# DaughterBoard.net
KiCad netlist of a schematic drawn in Altium Designer
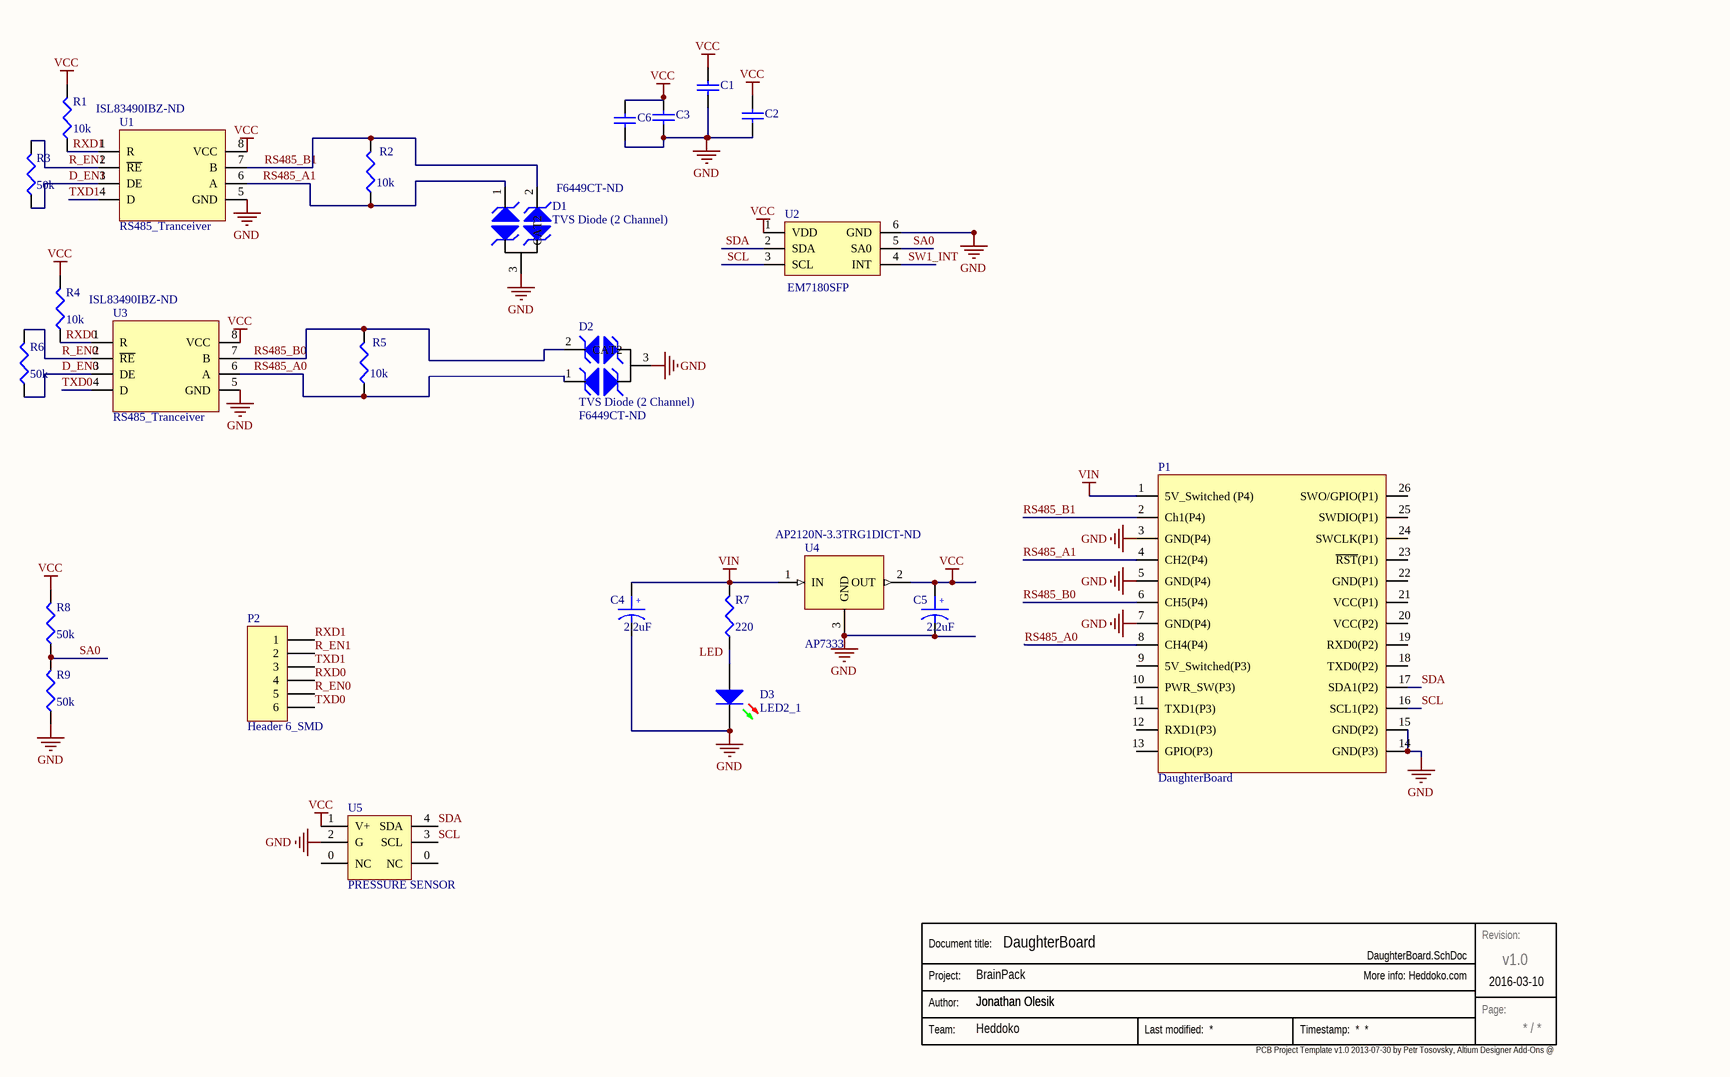
[diagram p0: DaughterBoard.SchDoc]

(export (version "E")
  (design (tool "Eeschema 10.0.6"))
  (components
    (comp (ref "C1")
      (value "Cap")
      (footprint "0603")
      (description "Capacitor")
      (fields (field (name "PUBLISHER") "Altium Limited"))
      (libsource (lib "SenaCorpLibSCH") (part "Cap"))
    )
    (comp (ref "C2")
      (value "Cap")
      (footprint "0603")
      (description "Capacitor")
      (fields (field (name "PUBLISHER") "Altium Limited"))
      (libsource (lib "SenaCorpLibSCH") (part "Cap"))
    )
    (comp (ref "C3")
      (value "Cap")
      (footprint "0603")
      (description "Capacitor")
      (fields (field (name "PUBLISHER") "Altium Limited"))
      (libsource (lib "SenaCorpLibSCH") (part "Cap"))
    )
    (comp (ref "C4")
      (value "2.2uF")
      (footprint "SMD0805")
      (fields
        (field (name "TOLERANCE") "±20%")
        (field (name "MANUFACTURER") "AVX Corporation")
        (field (name "MANUFACTURER PART NUMBER") "F921A225MPA")
      )
      (libsource (lib "AltiumDbLib") (part "CAP-POL"))
    )
    (comp (ref "C5")
      (value "2.2uF")
      (footprint "SMD0805")
      (fields
        (field (name "TOLERANCE") "±20%")
        (field (name "MANUFACTURER") "AVX Corporation")
        (field (name "MANUFACTURER PART NUMBER") "F921A225MPA")
      )
      (libsource (lib "AltiumDbLib") (part "CAP-POL"))
    )
    (comp (ref "C6")
      (value "Cap")
      (footprint "0603")
      (description "Capacitor")
      (fields (field (name "PUBLISHER") "Altium Limited"))
      (libsource (lib "SenaCorpLibSCH") (part "Cap"))
    )
    (comp (ref "D1")
      (value "TVS Diode (2 Channel)")
      (footprint "SOT23-3")
      (fields
        (field (name "SUPPLIER PART NUMBER") "F6449CT-ND")
        (field (name "MANUFACTURER PART NUMBER") "SM24CANA-02HTG")
        (field (name "MANUFACTURER") "Littelfuse Inc.")
      )
      (libsource (lib "SenaCorpLibSCH") (part "TVS Diode (2 Channel)"))
    )
    (comp (ref "D2")
      (value "TVS Diode (2 Channel)")
      (footprint "SOT23-3")
      (fields
        (field (name "SUPPLIER PART NUMBER") "F6449CT-ND")
        (field (name "MANUFACTURER PART NUMBER") "SM24CANA-02HTG")
        (field (name "MANUFACTURER") "Littelfuse Inc.")
      )
      (libsource (lib "SenaCorpLibSCH") (part "TVS Diode (2 Channel)"))
    )
    (comp (ref "D3")
      (value "LED2_1")
      (footprint "LED0603")
      (description "Typical RED, GREEN, YELLOW, AMBER GaAs LED")
      (fields (field (name "PUBLISHER") "Altium Limited"))
      (libsource (lib "SenaCorpLibSCH") (part "LED2_1"))
    )
    (comp (ref "P1")
      (value "DaughterBoard")
      (footprint "PowerBoardDaughter")
      (libsource (lib "SenaCorpLibSCH") (part "DaughterBoard"))
    )
    (comp (ref "P2")
      (value "Header 6_SMD")
      (footprint "Header 6 1.27mm")
      (description "Header, 6-Pin SMD")
      (fields (field (name "PUBLISHER") "Altium Limited"))
      (libsource (lib "SenaCorpLibSCH") (part "Header 6_SMD"))
    )
    (comp (ref "R1")
      (value "10k")
      (footprint "0603")
      (description "Resistor")
      (fields (field (name "PUBLISHER") "Altium Limited"))
      (libsource (lib "SenaCorpLibSCH") (part "Res3"))
    )
    (comp (ref "R2")
      (value "10k")
      (footprint "0402")
      (description "Resistor")
      (fields (field (name "PUBLISHER") "Altium Limited"))
      (libsource (lib "SenaCorpLibSCH") (part "Res3"))
    )
    (comp (ref "R3")
      (value "50k")
      (footprint "0402")
      (description "Resistor")
      (fields (field (name "PUBLISHER") "Altium Limited"))
      (libsource (lib "SenaCorpLibSCH") (part "Res3"))
    )
    (comp (ref "R4")
      (value "10k")
      (footprint "0603")
      (description "Resistor")
      (fields (field (name "PUBLISHER") "Altium Limited"))
      (libsource (lib "SenaCorpLibSCH") (part "Res3"))
    )
    (comp (ref "R5")
      (value "10k")
      (footprint "0402")
      (description "Resistor")
      (fields (field (name "PUBLISHER") "Altium Limited"))
      (libsource (lib "SenaCorpLibSCH") (part "Res3"))
    )
    (comp (ref "R6")
      (value "50k")
      (footprint "0402")
      (description "Resistor")
      (fields (field (name "PUBLISHER") "Altium Limited"))
      (libsource (lib "SenaCorpLibSCH") (part "Res3"))
    )
    (comp (ref "R7")
      (value "220")
      (footprint "0603")
      (description "Resistor")
      (fields (field (name "PUBLISHER") "Altium Limited"))
      (libsource (lib "SenaCorpLibSCH") (part "Res3"))
    )
    (comp (ref "R8")
      (value "50k")
      (footprint "0402")
      (description "Resistor")
      (fields (field (name "PUBLISHER") "Altium Limited"))
      (libsource (lib "SenaCorpLibSCH") (part "Res3"))
    )
    (comp (ref "R9")
      (value "50k")
      (footprint "0402")
      (description "Resistor")
      (fields (field (name "PUBLISHER") "Altium Limited"))
      (libsource (lib "SenaCorpLibSCH") (part "Res3"))
    )
    (comp (ref "Stamp") (value "Stamp") (libsource (lib "ShieldsLib") (part "Stamp")))
    (comp (ref "U1")
      (value "RS485_Tranceiver")
      (footprint "SOIC8")
      (fields
        (field (name "SUPPLIER PART NUMBER") "ISL83490IBZ-ND")
        (field (name "MANUFACTURER PART NUMBER") "ISL83490IBZ")
        (field (name "MANUFACTURER") "Intersil")
      )
      (libsource (lib "SenaCorpLibSCH") (part "RS485_Tranceiver"))
    )
    (comp (ref "U2")
      (value "EM7180SFP")
      (footprint "EM7180SFP")
      (libsource (lib "SenaCorpLibSCH") (part "EM7180SFP"))
    )
    (comp (ref "U3")
      (value "RS485_Tranceiver")
      (footprint "SOIC8")
      (fields
        (field (name "SUPPLIER PART NUMBER") "ISL83490IBZ-ND")
        (field (name "MANUFACTURER PART NUMBER") "ISL83490IBZ")
        (field (name "MANUFACTURER") "Intersil")
      )
      (libsource (lib "SenaCorpLibSCH") (part "RS485_Tranceiver"))
    )
    (comp (ref "U4")
      (value "AP7333")
      (footprint "SOT23-3")
      (description "3.3 V regulator")
      (fields
        (field (name "MANUFACTURER") "Diodes Incorporated")
        (field (name "MANUFACTURER PART NUMBER") "AP2120N-3.3TRG1")
        (field (name "SUPPLIER PART NUMBER") "AP2120N-3.3TRG1DICT-ND")
      )
      (libsource (lib "SenaCorpLibSCH") (part "AP7333"))
    )
    (comp (ref "U5")
      (value "PRESSURE SENSOR")
      (footprint "NPA-201")
      (description "NPA-201-EV")
      (libsource (lib "SenaCorpLibSCH") (part "NPA-201"))
    )
  )
  (nets
    (net (code "1") (name "/D_EN0") (class "Default")
      (node (ref "R6") (pin "1") (pinfunction "1_1") (pintype "passive"))
      (node (ref "U3") (pin "3") (pinfunction "DE_3") (pintype "passive"))
    )
    (net (code "2") (name "/D_EN1") (class "Default")
      (node (ref "R3") (pin "1") (pinfunction "1_1") (pintype "passive"))
      (node (ref "U1") (pin "3") (pinfunction "DE_3") (pintype "passive"))
    )
    (net (code "4") (name "/RS485_A0") (class "Default")
      (node (ref "D2") (pin "1") (pinfunction "CAT1_1") (pintype "passive"))
      (node (ref "P1") (pin "8") (pinfunction "CH4(P4)_8") (pintype "passive"))
      (node (ref "R5") (pin "1") (pinfunction "1_1") (pintype "passive"))
      (node (ref "U3") (pin "6") (pinfunction "A_6") (pintype "passive"))
    )
    (net (code "5") (name "/RS485_A1") (class "Default")
      (node (ref "D1") (pin "1") (pinfunction "CAT1_1") (pintype "passive"))
      (node (ref "P1") (pin "4") (pinfunction "CH2(P4)_4") (pintype "passive"))
      (node (ref "R2") (pin "1") (pinfunction "1_1") (pintype "passive"))
      (node (ref "U1") (pin "6") (pinfunction "A_6") (pintype "passive"))
    )
    (net (code "6") (name "/RS485_B0") (class "Default")
      (node (ref "D2") (pin "2") (pinfunction "CAT2_2") (pintype "passive"))
      (node (ref "P1") (pin "6") (pinfunction "CH5(P4)_6") (pintype "passive"))
      (node (ref "R5") (pin "2") (pinfunction "2_2") (pintype "passive"))
      (node (ref "U3") (pin "7") (pinfunction "B_7") (pintype "passive"))
    )
    (net (code "7") (name "/RS485_B1") (class "Default")
      (node (ref "D1") (pin "2") (pinfunction "CAT2_2") (pintype "passive"))
      (node (ref "P1") (pin "2") (pinfunction "Ch1(P4)_2") (pintype "passive"))
      (node (ref "R2") (pin "2") (pinfunction "2_2") (pintype "passive"))
      (node (ref "U1") (pin "7") (pinfunction "B_7") (pintype "passive"))
    )
    (net (code "8") (name "/RXD0") (class "Default")
      (node (ref "P2") (pin "4") (pinfunction "4_4") (pintype "passive"))
      (node (ref "R4") (pin "1") (pinfunction "1_1") (pintype "passive"))
      (node (ref "U3") (pin "1") (pinfunction "R_1") (pintype "passive"))
    )
    (net (code "9") (name "/RXD1") (class "Default")
      (node (ref "P2") (pin "1") (pinfunction "1_1") (pintype "passive"))
      (node (ref "R1") (pin "1") (pinfunction "1_1") (pintype "passive"))
      (node (ref "U1") (pin "1") (pinfunction "R_1") (pintype "passive"))
    )
    (net (code "10") (name "/R_EN0") (class "Default")
      (node (ref "P2") (pin "5") (pinfunction "5_5") (pintype "passive"))
      (node (ref "R6") (pin "2") (pinfunction "2_2") (pintype "passive"))
      (node (ref "U3") (pin "2") (pinfunction "~{RE}_2") (pintype "passive"))
    )
    (net (code "11") (name "/R_EN1") (class "Default")
      (node (ref "P2") (pin "2") (pinfunction "2_2") (pintype "passive"))
      (node (ref "R3") (pin "2") (pinfunction "2_2") (pintype "passive"))
      (node (ref "U1") (pin "2") (pinfunction "~{RE}_2") (pintype "passive"))
    )
    (net (code "12") (name "/SA0") (class "Default")
      (node (ref "R8") (pin "1") (pinfunction "1_1") (pintype "passive"))
      (node (ref "R9") (pin "2") (pinfunction "2_2") (pintype "passive"))
      (node (ref "U2") (pin "5") (pinfunction "SA0_5") (pintype "passive"))
    )
    (net (code "13") (name "/SCL") (class "Default")
      (node (ref "P1") (pin "16") (pinfunction "SCL1(P2)_16") (pintype "passive"))
      (node (ref "U2") (pin "3") (pinfunction "SCL_3") (pintype "passive"))
      (node (ref "U5") (pin "3") (pinfunction "SCL_3") (pintype "passive"))
    )
    (net (code "14") (name "/SDA") (class "Default")
      (node (ref "P1") (pin "17") (pinfunction "SDA1(P2)_17") (pintype "passive"))
      (node (ref "U2") (pin "2") (pinfunction "SDA_2") (pintype "passive"))
      (node (ref "U5") (pin "4") (pinfunction "SDA_4") (pintype "passive"))
    )
    (net (code "15") (name "/SW1_INT") (class "Default")
      (node (ref "U2") (pin "4") (pinfunction "INT_4") (pintype "passive"))
    )
    (net (code "16") (name "/TXD0") (class "Default")
      (node (ref "P2") (pin "6") (pinfunction "6_6") (pintype "passive"))
      (node (ref "U3") (pin "4") (pinfunction "D_4") (pintype "passive"))
    )
    (net (code "17") (name "/TXD1") (class "Default")
      (node (ref "P2") (pin "3") (pinfunction "3_3") (pintype "passive"))
      (node (ref "U1") (pin "4") (pinfunction "D_4") (pintype "passive"))
    )
    (net (code "18") (name "GND") (class "Default")
      (node (ref "C1") (pin "1") (pinfunction "1_1") (pintype "passive"))
      (node (ref "C2") (pin "1") (pinfunction "1_1") (pintype "passive"))
      (node (ref "C3") (pin "1") (pinfunction "1_1") (pintype "passive"))
      (node (ref "C4") (pin "2") (pinfunction "2_2") (pintype "passive"))
      (node (ref "C5") (pin "2") (pinfunction "2_2") (pintype "passive"))
      (node (ref "C6") (pin "1") (pinfunction "1_1") (pintype "passive"))
      (node (ref "D1") (pin "3") (pinfunction "Double_Cat_3") (pintype "passive"))
      (node (ref "D2") (pin "3") (pinfunction "Double_Cat_3") (pintype "passive"))
      (node (ref "D3") (pin "2") (pinfunction "K_2") (pintype "passive"))
      (node (ref "P1") (pin "14") (pinfunction "GND(P3)_14") (pintype "passive"))
      (node (ref "P1") (pin "15") (pinfunction "GND(P2)_15") (pintype "passive"))
      (node (ref "P1") (pin "3") (pinfunction "GND(P4)_3") (pintype "passive"))
      (node (ref "P1") (pin "5") (pinfunction "GND(P4)_5") (pintype "passive"))
      (node (ref "P1") (pin "7") (pinfunction "GND(P4)_7") (pintype "passive"))
      (node (ref "R9") (pin "1") (pinfunction "1_1") (pintype "passive"))
      (node (ref "U1") (pin "5") (pinfunction "GND_5") (pintype "passive"))
      (node (ref "U2") (pin "6") (pinfunction "GND_6") (pintype "passive"))
      (node (ref "U3") (pin "5") (pinfunction "GND_5") (pintype "passive"))
      (node (ref "U4") (pin "3") (pinfunction "GND_3") (pintype "passive"))
      (node (ref "U5") (pin "2") (pinfunction "G_2") (pintype "passive"))
    )
    (net (code "19") (name "Net-(D3-A)") (class "Default")
      (node (ref "D3") (pin "1") (pinfunction "A_1") (pintype "passive"))
      (node (ref "R7") (pin "1") (pinfunction "1_1") (pintype "passive"))
    )
    (net (code "20") (name "VCC") (class "Default")
      (node (ref "C1") (pin "2") (pinfunction "2_2") (pintype "passive"))
      (node (ref "C2") (pin "2") (pinfunction "2_2") (pintype "passive"))
      (node (ref "C3") (pin "2") (pinfunction "2_2") (pintype "passive"))
      (node (ref "C5") (pin "1") (pinfunction "1_1") (pintype "passive"))
      (node (ref "C6") (pin "2") (pinfunction "2_2") (pintype "passive"))
      (node (ref "R1") (pin "2") (pinfunction "2_2") (pintype "passive"))
      (node (ref "R4") (pin "2") (pinfunction "2_2") (pintype "passive"))
      (node (ref "R8") (pin "2") (pinfunction "2_2") (pintype "passive"))
      (node (ref "U1") (pin "8") (pinfunction "VCC_8") (pintype "passive"))
      (node (ref "U2") (pin "1") (pinfunction "VDD_1") (pintype "passive"))
      (node (ref "U3") (pin "8") (pinfunction "VCC_8") (pintype "passive"))
      (node (ref "U4") (pin "2") (pinfunction "OUT_2") (pintype "output"))
      (node (ref "U5") (pin "1") (pinfunction "V+_1") (pintype "passive"))
    )
    (net (code "21") (name "VIN") (class "Default")
      (node (ref "C4") (pin "1") (pinfunction "1_1") (pintype "passive"))
      (node (ref "P1") (pin "1") (pinfunction "5V_Switched_(P4)_1") (pintype "passive"))
      (node (ref "R7") (pin "2") (pinfunction "2_2") (pintype "passive"))
      (node (ref "U4") (pin "1") (pinfunction "IN_1") (pintype "input"))
    )
    (net (code "22") (name "unconnected-(P1-5V_Switched(P3)-Pad9)") (class "Default")
      (node (ref "P1") (pin "9") (pinfunction "5V_Switched(P3)_9") (pintype "passive"))
    )
    (net (code "23") (name "unconnected-(P1-GND(P1)-Pad22)") (class "Default")
      (node (ref "P1") (pin "22") (pinfunction "GND(P1)_22") (pintype "passive"))
    )
    (net (code "24") (name "unconnected-(P1-GPIO(P3)-Pad13)") (class "Default")
      (node (ref "P1") (pin "13") (pinfunction "GPIO(P3)_13") (pintype "passive"))
    )
    (net (code "25") (name "unconnected-(P1-PWR_SW(P3)-Pad10)") (class "Default")
      (node (ref "P1") (pin "10") (pinfunction "PWR_SW(P3)_10") (pintype "passive"))
    )
    (net (code "26") (name "unconnected-(P1-RXD0(P2)-Pad19)") (class "Default")
      (node (ref "P1") (pin "19") (pinfunction "RXD0(P2)_19") (pintype "passive"))
    )
    (net (code "27") (name "unconnected-(P1-RXD1(P3)-Pad12)") (class "Default")
      (node (ref "P1") (pin "12") (pinfunction "RXD1(P3)_12") (pintype "passive"))
    )
    (net (code "28") (name "unconnected-(P1-SWCLK(P1)-Pad24)") (class "Default")
      (node (ref "P1") (pin "24") (pinfunction "SWCLK(P1)_24") (pintype "passive"))
    )
    (net (code "29") (name "unconnected-(P1-SWDIO(P1)-Pad25)") (class "Default")
      (node (ref "P1") (pin "25") (pinfunction "SWDIO(P1)_25") (pintype "passive"))
    )
    (net (code "30") (name "unconnected-(P1-SWO{slash}GPIO(P1)-Pad26)") (class "Default")
      (node (ref "P1") (pin "26") (pinfunction "SWO/GPIO(P1)_26") (pintype "passive"))
    )
    (net (code "31") (name "unconnected-(P1-TXD0(P2)-Pad18)") (class "Default")
      (node (ref "P1") (pin "18") (pinfunction "TXD0(P2)_18") (pintype "passive"))
    )
    (net (code "32") (name "unconnected-(P1-TXD1(P3)-Pad11)") (class "Default")
      (node (ref "P1") (pin "11") (pinfunction "TXD1(P3)_11") (pintype "passive"))
    )
    (net (code "33") (name "unconnected-(P1-VCC(P1)-Pad21)") (class "Default")
      (node (ref "P1") (pin "21") (pinfunction "VCC(P1)_21") (pintype "passive"))
    )
    (net (code "34") (name "unconnected-(P1-VCC(P2)-Pad20)") (class "Default")
      (node (ref "P1") (pin "20") (pinfunction "VCC(P2)_20") (pintype "passive"))
    )
    (net (code "35") (name "unconnected-(P1-~{RST}(P1)-Pad23)") (class "Default")
      (node (ref "P1") (pin "23") (pinfunction "~{RST}(P1)_23") (pintype "passive"))
    )
    (net (code "36") (name "unconnected-(U5-NC-Pad0)") (class "Default")
      (node (ref "U5") (pin "0") (pinfunction "NC_0") (pintype "passive"))
    )
    (net (code "37") (name "unconnected-(U5-NC-Pad0)_1") (class "Default")
      (node (ref "U5") (pin "0") (pinfunction "NC_0") (pintype "passive"))
    )
  )
)
